# SchV2-4cap.net
KiCad netlist of a schematic drawn in Altium Designer
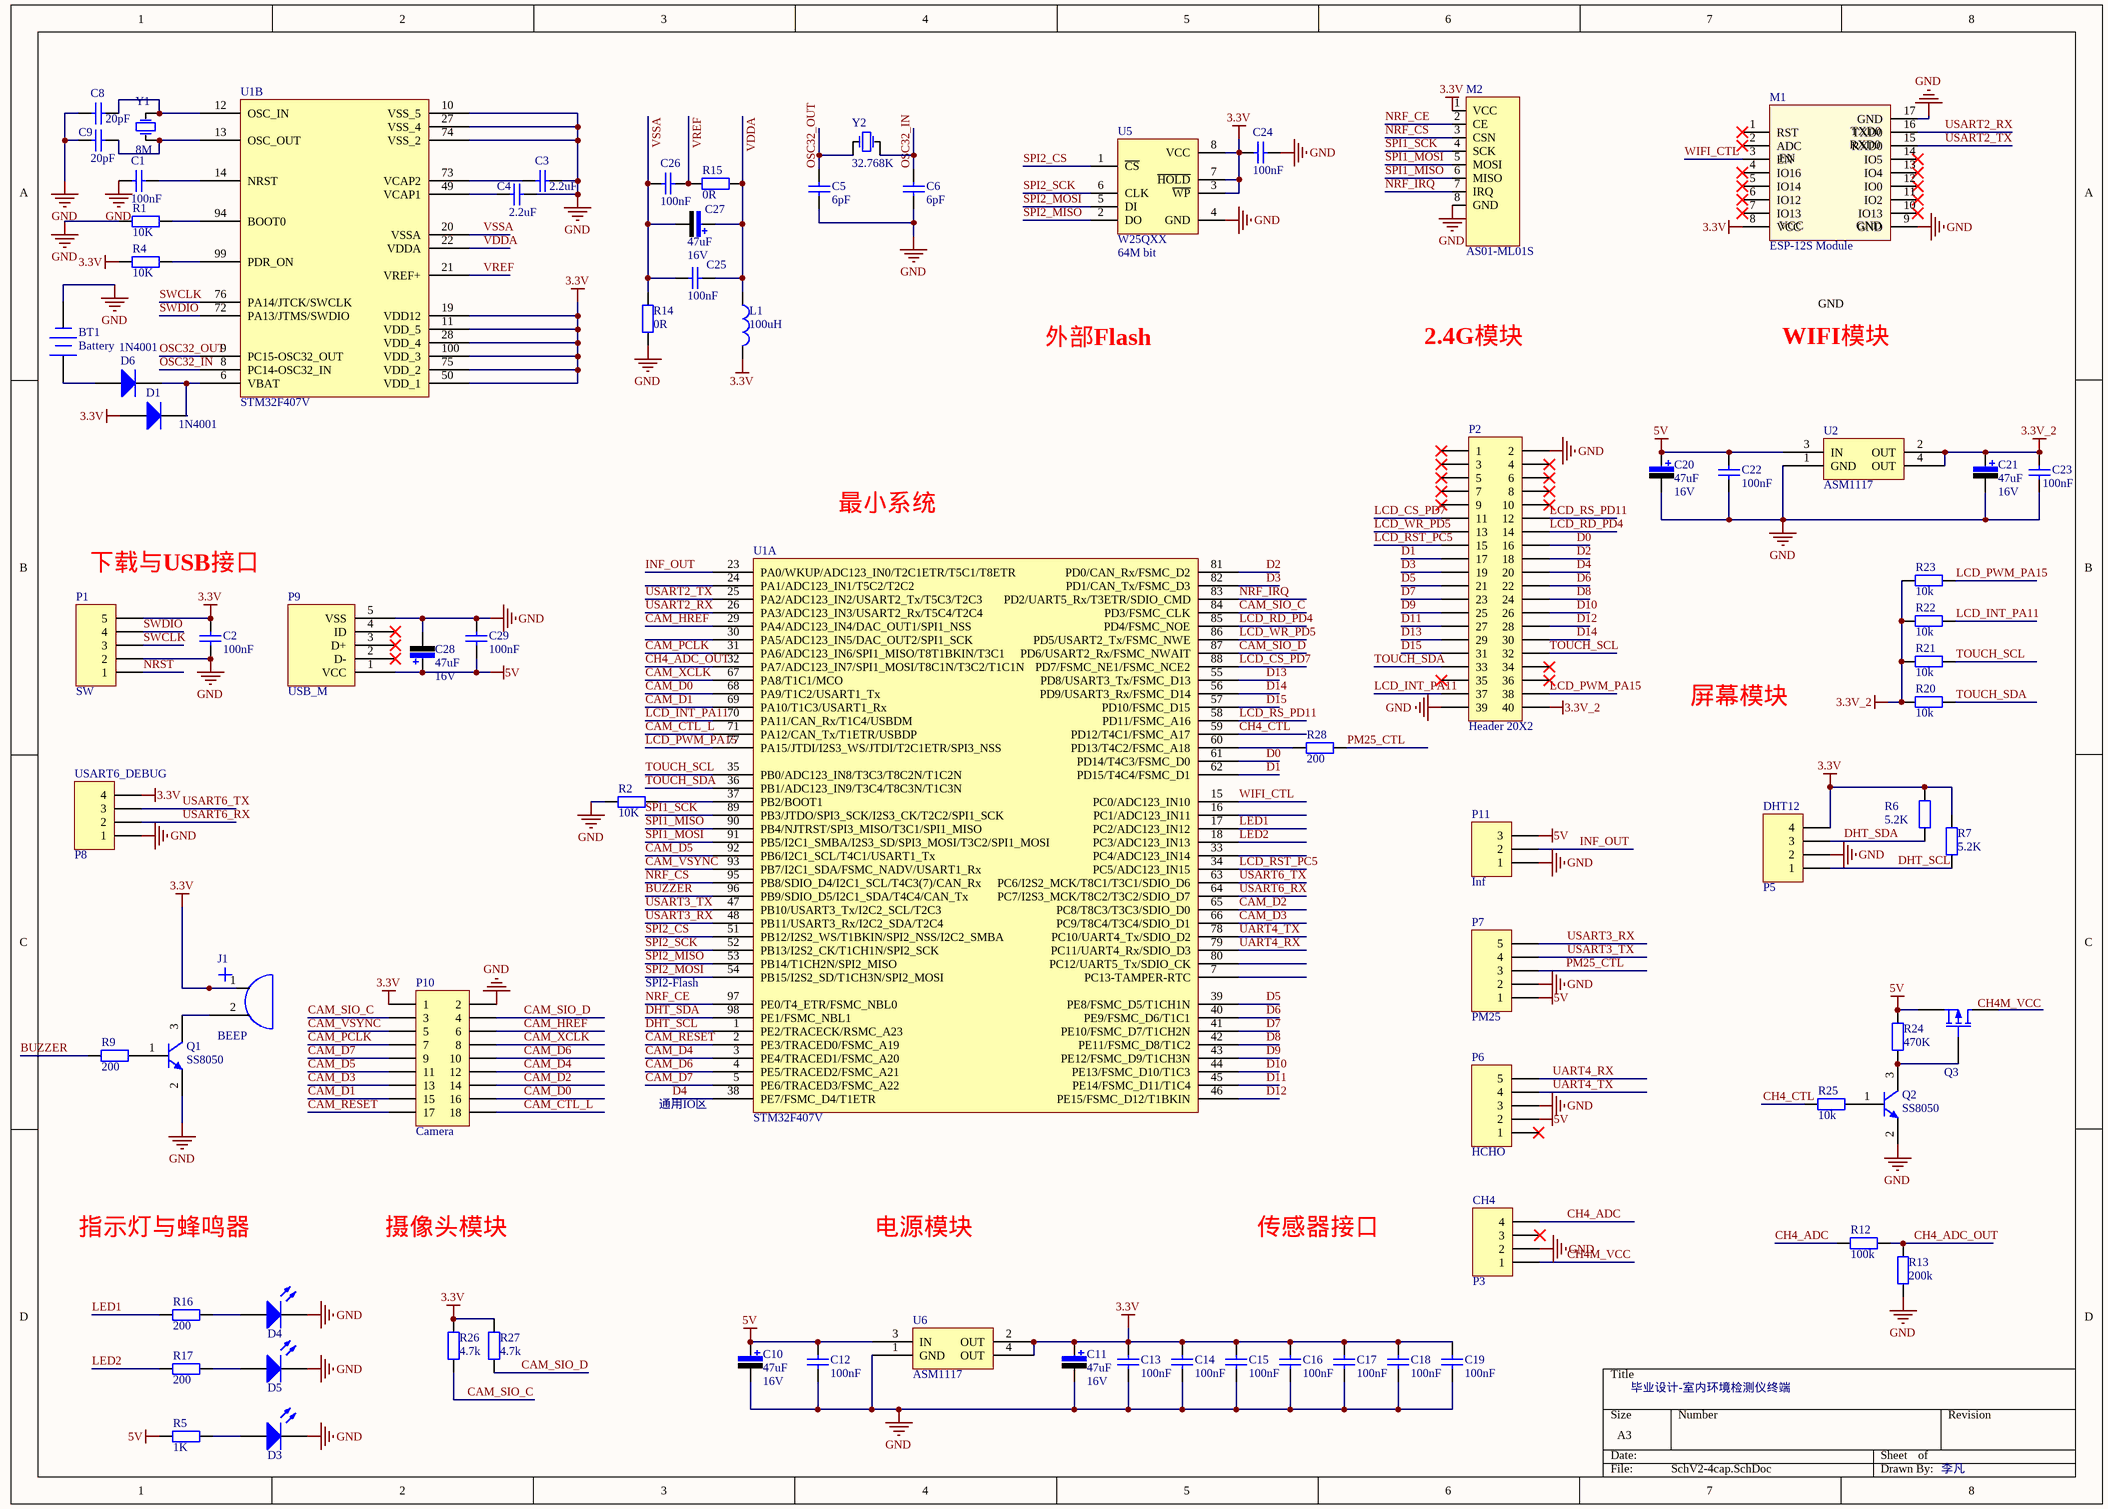
[diagram p0: SchV2-4cap.SchDoc]

(export (version "E")
  (design (tool "Eeschema 10.0.6"))
  (components
    (comp (ref "BT1")
      (value "Battery")
      (footprint "CR1220")
      (description "备份电池")
      (libsource (lib "Fszhang") (part "Battery"))
    )
    (comp (ref "C1")
      (value "100nF")
      (footprint "C-RAD-0603")
      (description "无极性电容")
      (fields (field (name "Comment") "Cap"))
      (libsource (lib "Fszhang") (part "Cap"))
    )
    (comp (ref "C2")
      (value "100nF")
      (footprint "C-RAD-0603")
      (description "无极性电容")
      (fields (field (name "Comment") "Cap"))
      (libsource (lib "Fszhang") (part "Cap"))
    )
    (comp (ref "C3")
      (value "2.2uF")
      (footprint "C-RAD-0603")
      (description "无极性电容")
      (fields (field (name "Comment") "Cap"))
      (libsource (lib "Fszhang") (part "Cap"))
    )
    (comp (ref "C4")
      (value "2.2uF")
      (footprint "C-RAD-0603")
      (description "无极性电容")
      (fields (field (name "Comment") "Cap"))
      (libsource (lib "Fszhang") (part "Cap"))
    )
    (comp (ref "C5")
      (value "6pF")
      (footprint "C-RAD-0603")
      (description "无极性电容")
      (fields (field (name "Comment") "Cap"))
      (libsource (lib "Fszhang") (part "Cap"))
    )
    (comp (ref "C6")
      (value "6pF")
      (footprint "C-RAD-0603")
      (description "无极性电容")
      (fields (field (name "Comment") "Cap"))
      (libsource (lib "Fszhang") (part "Cap"))
    )
    (comp (ref "C8")
      (value "20pF")
      (footprint "C-RAD-0603")
      (description "无极性电容")
      (fields (field (name "Comment") "Cap"))
      (libsource (lib "Fszhang") (part "Cap"))
    )
    (comp (ref "C9")
      (value "20pF")
      (footprint "C-RAD-0603")
      (description "无极性电容")
      (fields (field (name "Comment") "Cap"))
      (libsource (lib "Fszhang") (part "Cap"))
    )
    (comp (ref "C10")
      (value "47uF")
      (footprint "CAP-3528")
      (description "极性电解电容")
      (fields (field (name "VOL") "16V") (field (name "Comment") "Cap Pol"))
      (libsource (lib "Fszhang") (part "Cap Pol"))
    )
    (comp (ref "C11")
      (value "47uF")
      (footprint "CAP-3528")
      (description "极性电解电容")
      (fields (field (name "VOL") "16V") (field (name "Comment") "Cap Pol"))
      (libsource (lib "Fszhang") (part "Cap Pol"))
    )
    (comp (ref "C12")
      (value "100nF")
      (footprint "C-RAD-0603")
      (description "无极性电容")
      (fields (field (name "Comment") "Cap"))
      (libsource (lib "Fszhang") (part "Cap"))
    )
    (comp (ref "C13")
      (value "100nF")
      (footprint "C-RAD-0603")
      (description "无极性电容")
      (fields (field (name "Comment") "Cap"))
      (libsource (lib "Fszhang") (part "Cap"))
    )
    (comp (ref "C14")
      (value "100nF")
      (footprint "C-RAD-0603")
      (description "无极性电容")
      (fields (field (name "Comment") "Cap"))
      (libsource (lib "Fszhang") (part "Cap"))
    )
    (comp (ref "C15")
      (value "100nF")
      (footprint "C-RAD-0603")
      (description "无极性电容")
      (fields (field (name "Comment") "Cap"))
      (libsource (lib "Fszhang") (part "Cap"))
    )
    (comp (ref "C16")
      (value "100nF")
      (footprint "C-RAD-0603")
      (description "无极性电容")
      (fields (field (name "Comment") "Cap"))
      (libsource (lib "Fszhang") (part "Cap"))
    )
    (comp (ref "C17")
      (value "100nF")
      (footprint "C-RAD-0603")
      (description "无极性电容")
      (fields (field (name "Comment") "Cap"))
      (libsource (lib "Fszhang") (part "Cap"))
    )
    (comp (ref "C18")
      (value "100nF")
      (footprint "C-RAD-0603")
      (description "无极性电容")
      (fields (field (name "Comment") "Cap"))
      (libsource (lib "Fszhang") (part "Cap"))
    )
    (comp (ref "C19")
      (value "100nF")
      (footprint "C-RAD-0603")
      (description "无极性电容")
      (fields (field (name "Comment") "Cap"))
      (libsource (lib "Fszhang") (part "Cap"))
    )
    (comp (ref "C20")
      (value "47uF")
      (footprint "CAP-3528")
      (description "极性电解电容")
      (fields (field (name "VOL") "16V") (field (name "Comment") "Cap Pol"))
      (libsource (lib "Fszhang") (part "Cap Pol"))
    )
    (comp (ref "C21")
      (value "47uF")
      (footprint "CAP-3528")
      (description "极性电解电容")
      (fields (field (name "VOL") "16V") (field (name "Comment") "Cap Pol"))
      (libsource (lib "Fszhang") (part "Cap Pol"))
    )
    (comp (ref "C22")
      (value "100nF")
      (footprint "C-RAD-0603")
      (description "无极性电容")
      (fields (field (name "Comment") "Cap"))
      (libsource (lib "Fszhang") (part "Cap"))
    )
    (comp (ref "C23")
      (value "100nF")
      (footprint "C-RAD-0603")
      (description "无极性电容")
      (fields (field (name "Comment") "Cap"))
      (libsource (lib "Fszhang") (part "Cap"))
    )
    (comp (ref "C24")
      (value "100nF")
      (footprint "C-RAD-0603")
      (description "无极性电容")
      (fields (field (name "Comment") "Cap"))
      (libsource (lib "Fszhang") (part "Cap"))
    )
    (comp (ref "C25")
      (value "100nF")
      (footprint "C-RAD-0603")
      (description "无极性电容")
      (fields (field (name "Comment") "Cap"))
      (libsource (lib "Fszhang") (part "Cap"))
    )
    (comp (ref "C26")
      (value "100nF")
      (footprint "C-RAD-0603")
      (description "无极性电容")
      (fields (field (name "Comment") "Cap"))
      (libsource (lib "Fszhang") (part "Cap"))
    )
    (comp (ref "C27")
      (value "47uF")
      (footprint "CAP-3528")
      (description "极性电解电容")
      (fields (field (name "VOL") "16V") (field (name "Comment") "Cap Pol"))
      (libsource (lib "") (part "Cap Pol_2"))
    )
    (comp (ref "C28")
      (value "47uF")
      (footprint "CAP-3528")
      (description "极性电解电容")
      (fields (field (name "VOL") "16V") (field (name "Comment") "Cap Pol"))
      (libsource (lib "") (part "Cap Pol_1"))
    )
    (comp (ref "C29")
      (value "100nF")
      (footprint "C-RAD-0603")
      (description "无极性电容")
      (fields (field (name "Comment") "Cap"))
      (libsource (lib "Fszhang") (part "Cap"))
    )
    (comp (ref "D1")
      (value "Diode")
      (footprint "DIODE-1206")
      (description "二极管")
      (fields (field (name "TYPE") "1N4001"))
      (libsource (lib "Fszhang") (part "Diode"))
    )
    (comp (ref "D3")
      (value "LED0")
      (footprint "LED_0805")
      (description "发光二极管")
      (libsource (lib "Fszhang") (part "LED0"))
    )
    (comp (ref "D4")
      (value "LED0")
      (footprint "LED_0805")
      (description "发光二极管")
      (libsource (lib "Fszhang") (part "LED0"))
    )
    (comp (ref "D5")
      (value "LED0")
      (footprint "LED_0805")
      (description "发光二极管")
      (libsource (lib "Fszhang") (part "LED0"))
    )
    (comp (ref "D6")
      (value "Diode")
      (footprint "DIODE-1206")
      (description "二极管")
      (fields (field (name "TYPE") "1N4001"))
      (libsource (lib "Fszhang") (part "Diode"))
    )
    (comp (ref "J1")
      (value "BEEP")
      (footprint "Beep")
      (description "蜂鸣器")
      (libsource (lib "Fszhang") (part "BEEP"))
    )
    (comp (ref "L1")
      (value "100uH")
      (footprint "0805-1")
      (description "电感")
      (fields (field (name "Comment") "Inductor"))
      (libsource (lib "Fszhang") (part "Inductor"))
    )
    (comp (ref "M1")
      (value "ESP-12S Module")
      (footprint "ESP-12S Module")
      (libsource (lib "ESP-12S Module") (part "ESP-12S Module"))
    )
    (comp (ref "M2")
      (value "AS01-ML01S")
      (footprint "FanliPcbLib:AS01-ML01S")
      (description "贴片2.4G模块")
      (libsource (lib "Schlib") (part "AS01-ML01S"))
    )
    (comp (ref "P1")
      (value "SW")
      (footprint "FanliPcbLib:7-Header_7mm")
      (description "Header, 5-Pin")
      (libsource (lib "Miscellaneous Connectors") (part "Header 5"))
    )
    (comp (ref "P2")
      (value "Header 20X2")
      (footprint "HDR2X20")
      (description "Header, 20-Pin, Dual row")
      (libsource (lib "Miscellaneous Connectors") (part "Header 20X2"))
    )
    (comp (ref "P3")
      (value "CH4")
      (footprint "HDR4X1_A")
      (description "接插件")
      (libsource (lib "Fszhang") (part "Header 4"))
    )
    (comp (ref "P5")
      (value "DHT12")
      (footprint "HDR4X1_A")
      (description "接插件")
      (libsource (lib "Fszhang") (part "Header 4"))
    )
    (comp (ref "P6")
      (value "HCHO")
      (footprint "7-Header_7mm")
      (description "Header, 5-Pin")
      (libsource (lib "Miscellaneous Connectors") (part "Header 5"))
    )
    (comp (ref "P7")
      (value "PM25")
      (footprint "7-Header_7mm")
      (description "Header, 5-Pin")
      (libsource (lib "Miscellaneous Connectors") (part "Header 5"))
    )
    (comp (ref "P8")
      (value "USART6_DEBUG")
      (footprint "HDR4X1_A")
      (description "接插件")
      (libsource (lib "Fszhang") (part "Header 4"))
    )
    (comp (ref "P9")
      (value "USB_M")
      (footprint "USB_MICRO")
      (description "MicroUSB接口")
      (libsource (lib "Fszhang") (part "USB_M"))
    )
    (comp (ref "P10")
      (value "Camera")
      (footprint "HDR2X9")
      (description "Header, 9-Pin, Dual row")
      (libsource (lib "Miscellaneous Connectors") (part "Header 9X2"))
    )
    (comp (ref "P11")
      (value "Inf")
      (footprint "HDR1X3")
      (description "Header, 3-Pin")
      (libsource (lib "Miscellaneous Connectors") (part "Header 3"))
    )
    (comp (ref "Q1")
      (value "SS8050")
      (footprint "SOT-23")
      (description "NPN贴片三极管")
      (libsource (lib "Fszhang") (part "SS8050"))
    )
    (comp (ref "Q2")
      (value "SS8050")
      (footprint "SOT-23")
      (description "NPN贴片三极管")
      (libsource (lib "Fszhang") (part "SS8050"))
    )
    (comp (ref "Q3")
      (value "MOSFET-P")
      (footprint "TO-220AB")
      (description "P-Channel MOSFET")
      (libsource (lib "Fszhang") (part "MOSFET-P"))
    )
    (comp (ref "R1")
      (value "10K")
      (footprint "0603-1")
      (description "贴片电阻")
      (fields (field (name "Comment") "Res1"))
      (libsource (lib "Fszhang") (part "Res1"))
    )
    (comp (ref "R2")
      (value "10K")
      (footprint "0603-1")
      (description "贴片电阻")
      (fields (field (name "Comment") "Res1"))
      (libsource (lib "Fszhang") (part "Res1"))
    )
    (comp (ref "R4")
      (value "10K")
      (footprint "0603-1")
      (description "贴片电阻")
      (fields (field (name "Comment") "Res1"))
      (libsource (lib "Fszhang") (part "Res1"))
    )
    (comp (ref "R5")
      (value "1K")
      (footprint "0603-1")
      (description "贴片电阻")
      (fields (field (name "Comment") "Res1"))
      (libsource (lib "") (part "Res1_2"))
    )
    (comp (ref "R6")
      (value "5.2K")
      (footprint "0603-1")
      (description "贴片电阻")
      (fields (field (name "Comment") "Res1"))
      (libsource (lib "") (part "Res1_1"))
    )
    (comp (ref "R7")
      (value "5.2K")
      (footprint "0603-1")
      (description "贴片电阻")
      (fields (field (name "Comment") "Res1"))
      (libsource (lib "") (part "Res1_1"))
    )
    (comp (ref "R9")
      (value "200")
      (footprint "0603-1")
      (description "贴片电阻")
      (fields (field (name "Comment") "Res1"))
      (libsource (lib "") (part "Res1_2"))
    )
    (comp (ref "R12")
      (value "100k")
      (footprint "0603-1")
      (description "贴片电阻")
      (fields (field (name "Comment") "Res1"))
      (libsource (lib "Fszhang") (part "Res1"))
    )
    (comp (ref "R13")
      (value "200k")
      (footprint "0603-1")
      (description "贴片电阻")
      (fields (field (name "Comment") "Res1"))
      (libsource (lib "") (part "Res1_1"))
    )
    (comp (ref "R14")
      (value "0R")
      (footprint "0603-1")
      (description "贴片电阻")
      (fields (field (name "Comment") "Res1"))
      (libsource (lib "") (part "Res1_1"))
    )
    (comp (ref "R15")
      (value "0R")
      (footprint "0603-1")
      (description "贴片电阻")
      (fields (field (name "Comment") "Res1"))
      (libsource (lib "") (part "Res1_2"))
    )
    (comp (ref "R16")
      (value "200")
      (footprint "0603-1")
      (description "贴片电阻")
      (fields (field (name "Comment") "Res1"))
      (libsource (lib "") (part "Res1_2"))
    )
    (comp (ref "R17")
      (value "200")
      (footprint "0603-1")
      (description "贴片电阻")
      (fields (field (name "Comment") "Res1"))
      (libsource (lib "") (part "Res1_2"))
    )
    (comp (ref "R20")
      (value "10k")
      (footprint "0603-1")
      (description "贴片电阻")
      (fields (field (name "Comment") "Res1"))
      (libsource (lib "") (part "Res1_2"))
    )
    (comp (ref "R21")
      (value "10k")
      (footprint "0603-1")
      (description "贴片电阻")
      (fields (field (name "Comment") "Res1"))
      (libsource (lib "") (part "Res1_2"))
    )
    (comp (ref "R22")
      (value "10k")
      (footprint "0603-1")
      (description "贴片电阻")
      (fields (field (name "Comment") "Res1"))
      (libsource (lib "") (part "Res1_2"))
    )
    (comp (ref "R23")
      (value "10k")
      (footprint "0603-1")
      (description "贴片电阻")
      (fields (field (name "Comment") "Res1"))
      (libsource (lib "") (part "Res1_2"))
    )
    (comp (ref "R24")
      (value "470K")
      (footprint "0603-1")
      (description "贴片电阻")
      (fields (field (name "Comment") "Res1"))
      (libsource (lib "") (part "Res1_1"))
    )
    (comp (ref "R25")
      (value "10k")
      (footprint "0603-1")
      (description "贴片电阻")
      (fields (field (name "Comment") "Res1"))
      (libsource (lib "") (part "Res1_2"))
    )
    (comp (ref "R26")
      (value "4.7k")
      (footprint "0603-1")
      (description "贴片电阻")
      (fields (field (name "Comment") "Res1"))
      (libsource (lib "") (part "Res1_1"))
    )
    (comp (ref "R27")
      (value "4.7k")
      (footprint "0603-1")
      (description "贴片电阻")
      (fields (field (name "Comment") "Res1"))
      (libsource (lib "") (part "Res1_3"))
    )
    (comp (ref "R28")
      (value "200")
      (footprint "0603-1")
      (description "贴片电阻")
      (fields (field (name "Comment") "Res1"))
      (libsource (lib "Fszhang") (part "Res1"))
    )
    (comp (ref "U1")
      (value "STM32F407V")
      (footprint "LQFP-100_M")
      (description "STM32单片机100引脚")
      (libsource (lib "Fszhang") (part "STM32F407V"))
    )
    (comp (ref "U2")
      (value "ASM1117")
      (footprint "SOT-223")
      (description "3.3V稳压芯片")
      (libsource (lib "Fszhang") (part "ASM1117"))
    )
    (comp (ref "U5")
      (value "W25QXX")
      (footprint "SOIC8_W")
      (description "SPI FLASH")
      (fields (field (name "MEMORY") "64M bit"))
      (libsource (lib "Fszhang") (part "W25QXX"))
    )
    (comp (ref "U6")
      (value "ASM1117")
      (footprint "SOT-223")
      (description "3.3V稳压芯片")
      (libsource (lib "Fszhang") (part "ASM1117"))
    )
    (comp (ref "Y1")
      (value "8M")
      (footprint "X-SM49")
      (description "晶振")
      (fields (field (name "Comment") "XTAL"))
      (libsource (lib "Fszhang") (part "XTAL"))
    )
    (comp (ref "Y2")
      (value "32.768K")
      (footprint "MC-306")
      (description "晶振")
      (fields (field (name "Comment") "XTAL"))
      (libsource (lib "Fszhang") (part "XTAL"))
    )
  )
  (nets
    (net (code "1") (name "/BUZZER") (class "Default")
      (node (ref "R9") (pin "2") (pinfunction "2_2") (pintype "passive"))
      (node (ref "U1") (pin "96") (pinfunction "PB9/SDIO_D5/I2C1_SDA/T4C4/CAN_Tx_96") (pintype "passive"))
    )
    (net (code "2") (name "/CAM_CTL_L") (class "Default")
      (node (ref "P10") (pin "18") (pinfunction "18_18") (pintype "passive"))
      (node (ref "U1") (pin "71") (pinfunction "PA12/CAN_Tx/T1ETR/USBDP_71") (pintype "passive"))
    )
    (net (code "3") (name "/CAM_D0") (class "Default")
      (node (ref "P10") (pin "16") (pinfunction "16_16") (pintype "passive"))
      (node (ref "U1") (pin "68") (pinfunction "PA9/T1C2/USART1_Tx_68") (pintype "passive"))
    )
    (net (code "4") (name "/CAM_D1") (class "Default")
      (node (ref "P10") (pin "15") (pinfunction "15_15") (pintype "passive"))
      (node (ref "U1") (pin "69") (pinfunction "PA10/T1C3/USART1_Rx_69") (pintype "passive"))
    )
    (net (code "5") (name "/CAM_D2") (class "Default")
      (node (ref "P10") (pin "14") (pinfunction "14_14") (pintype "passive"))
      (node (ref "U1") (pin "65") (pinfunction "PC8/T8C3/T3C3/SDIO_D0_65") (pintype "passive"))
    )
    (net (code "6") (name "/CAM_D3") (class "Default")
      (node (ref "P10") (pin "13") (pinfunction "13_13") (pintype "passive"))
      (node (ref "U1") (pin "66") (pinfunction "PC9/T8C4/T3C4/SDIO_D1_66") (pintype "passive"))
    )
    (net (code "7") (name "/CAM_D4") (class "Default")
      (node (ref "P10") (pin "12") (pinfunction "12_12") (pintype "passive"))
      (node (ref "U1") (pin "3") (pinfunction "PE4/TRACED1/FSMC_A20_3") (pintype "passive"))
    )
    (net (code "8") (name "/CAM_D5") (class "Default")
      (node (ref "P10") (pin "11") (pinfunction "11_11") (pintype "passive"))
      (node (ref "U1") (pin "92") (pinfunction "PB6/I2C1_SCL/T4C1/USART1_Tx_92") (pintype "passive"))
    )
    (net (code "9") (name "/CAM_D6") (class "Default")
      (node (ref "P10") (pin "10") (pinfunction "10_10") (pintype "passive"))
      (node (ref "U1") (pin "4") (pinfunction "PE5/TRACED2/FSMC_A21_4") (pintype "passive"))
    )
    (net (code "10") (name "/CAM_D7") (class "Default")
      (node (ref "P10") (pin "9") (pinfunction "9_9") (pintype "passive"))
      (node (ref "U1") (pin "5") (pinfunction "PE6/TRACED3/FSMC_A22_5") (pintype "passive"))
    )
    (net (code "11") (name "/CAM_HREF") (class "Default")
      (node (ref "P10") (pin "6") (pinfunction "6_6") (pintype "passive"))
      (node (ref "U1") (pin "29") (pinfunction "PA4/ADC123_IN4/DAC_OUT1/SPI1_NSS_29") (pintype "passive"))
    )
    (net (code "12") (name "/CAM_PCLK") (class "Default")
      (node (ref "P10") (pin "7") (pinfunction "7_7") (pintype "passive"))
      (node (ref "U1") (pin "31") (pinfunction "PA6/ADC123_IN6/SPI1_MISO/T8T1BKIN/T3C1_31") (pintype "passive"))
    )
    (net (code "13") (name "/CAM_RESET") (class "Default")
      (node (ref "P10") (pin "17") (pinfunction "17_17") (pintype "passive"))
      (node (ref "U1") (pin "2") (pinfunction "PE3/TRACED0/FSMC_A19_2") (pintype "passive"))
    )
    (net (code "14") (name "/CAM_SIO_C") (class "Default")
      (node (ref "P10") (pin "3") (pinfunction "3_3") (pintype "passive"))
      (node (ref "R26") (pin "1") (pinfunction "1_1") (pintype "passive"))
      (node (ref "U1") (pin "84") (pinfunction "PD3/FSMC_CLK_84") (pintype "passive"))
    )
    (net (code "15") (name "/CAM_SIO_D") (class "Default")
      (node (ref "P10") (pin "4") (pinfunction "4_4") (pintype "passive"))
      (node (ref "R27") (pin "2") (pinfunction "2_2") (pintype "passive"))
      (node (ref "U1") (pin "87") (pinfunction "PD6/USART2_Rx/FSMC_NWAIT_87") (pintype "passive"))
    )
    (net (code "16") (name "/CAM_VSYNC") (class "Default")
      (node (ref "P10") (pin "5") (pinfunction "5_5") (pintype "passive"))
      (node (ref "U1") (pin "93") (pinfunction "PB7/I2C1_SDA/FSMC_NADV/USART1_Rx_93") (pintype "passive"))
    )
    (net (code "17") (name "/CAM_XCLK") (class "Default")
      (node (ref "P10") (pin "8") (pinfunction "8_8") (pintype "passive"))
      (node (ref "U1") (pin "67") (pinfunction "PA8/T1C1/MCO_67") (pintype "passive"))
    )
    (net (code "18") (name "/CH4M_VCC") (class "Default")
      (node (ref "P3") (pin "1") (pinfunction "1_1") (pintype "passive"))
    )
    (net (code "19") (name "/CH4_ADC") (class "Default")
      (node (ref "P3") (pin "4") (pinfunction "4_4") (pintype "passive"))
      (node (ref "R12") (pin "1") (pinfunction "1_1") (pintype "passive"))
    )
    (net (code "20") (name "/CH4_ADC_OUT") (class "Default")
      (node (ref "R12") (pin "2") (pinfunction "2_2") (pintype "passive"))
      (node (ref "R13") (pin "2") (pinfunction "2_2") (pintype "passive"))
      (node (ref "U1") (pin "32") (pinfunction "PA7/ADC123_IN7/SPI1_MOSI/T8C1N/T3C2/T1C1N_32") (pintype "passive"))
    )
    (net (code "21") (name "/CH4_CTL") (class "Default")
      (node (ref "R25") (pin "2") (pinfunction "2_2") (pintype "passive"))
      (node (ref "U1") (pin "59") (pinfunction "PD12/T4C1/FSMC_A17_59") (pintype "passive"))
    )
    (net (code "22") (name "/D0") (class "Default")
      (node (ref "P2") (pin "16") (pinfunction "16_16") (pintype "passive"))
      (node (ref "U1") (pin "61") (pinfunction "PD14/T4C3/FSMC_D0_61") (pintype "passive"))
    )
    (net (code "23") (name "/D1") (class "Default")
      (node (ref "P2") (pin "17") (pinfunction "17_17") (pintype "passive"))
      (node (ref "U1") (pin "62") (pinfunction "PD15/T4C4/FSMC_D1_62") (pintype "passive"))
    )
    (net (code "24") (name "/D2") (class "Default")
      (node (ref "P2") (pin "18") (pinfunction "18_18") (pintype "passive"))
      (node (ref "U1") (pin "81") (pinfunction "PD0/CAN_Rx/FSMC_D2_81") (pintype "passive"))
    )
    (net (code "25") (name "/D3") (class "Default")
      (node (ref "P2") (pin "19") (pinfunction "19_19") (pintype "passive"))
      (node (ref "U1") (pin "82") (pinfunction "PD1/CAN_Tx/FSMC_D3_82") (pintype "passive"))
    )
    (net (code "26") (name "/D4") (class "Default")
      (node (ref "P2") (pin "20") (pinfunction "20_20") (pintype "passive"))
      (node (ref "U1") (pin "38") (pinfunction "PE7/FSMC_D4/T1ETR_38") (pintype "passive"))
    )
    (net (code "27") (name "/D5") (class "Default")
      (node (ref "P2") (pin "21") (pinfunction "21_21") (pintype "passive"))
      (node (ref "U1") (pin "39") (pinfunction "PE8/FSMC_D5/T1CH1N_39") (pintype "passive"))
    )
    (net (code "28") (name "/D6") (class "Default")
      (node (ref "P2") (pin "22") (pinfunction "22_22") (pintype "passive"))
      (node (ref "U1") (pin "40") (pinfunction "PE9/FSMC_D6/T1C1_40") (pintype "passive"))
    )
    (net (code "29") (name "/D7") (class "Default")
      (node (ref "P2") (pin "23") (pinfunction "23_23") (pintype "passive"))
      (node (ref "U1") (pin "41") (pinfunction "PE10/FSMC_D7/T1CH2N_41") (pintype "passive"))
    )
    (net (code "30") (name "/D8") (class "Default")
      (node (ref "P2") (pin "24") (pinfunction "24_24") (pintype "passive"))
      (node (ref "U1") (pin "42") (pinfunction "PE11/FSMC_D8/T1C2_42") (pintype "passive"))
    )
    (net (code "31") (name "/D9") (class "Default")
      (node (ref "P2") (pin "25") (pinfunction "25_25") (pintype "passive"))
      (node (ref "U1") (pin "43") (pinfunction "PE12/FSMC_D9/T1CH3N_43") (pintype "passive"))
    )
    (net (code "32") (name "/D10") (class "Default")
      (node (ref "P2") (pin "26") (pinfunction "26_26") (pintype "passive"))
      (node (ref "U1") (pin "44") (pinfunction "PE13/FSMC_D10/T1C3_44") (pintype "passive"))
    )
    (net (code "33") (name "/D11") (class "Default")
      (node (ref "P2") (pin "27") (pinfunction "27_27") (pintype "passive"))
      (node (ref "U1") (pin "45") (pinfunction "PE14/FSMC_D11/T1C4_45") (pintype "passive"))
    )
    (net (code "34") (name "/D12") (class "Default")
      (node (ref "P2") (pin "28") (pinfunction "28_28") (pintype "passive"))
      (node (ref "U1") (pin "46") (pinfunction "PE15/FSMC_D12/T1BKIN_46") (pintype "passive"))
    )
    (net (code "35") (name "/D13") (class "Default")
      (node (ref "P2") (pin "29") (pinfunction "29_29") (pintype "passive"))
      (node (ref "U1") (pin "55") (pinfunction "PD8/USART3_Tx/FSMC_D13_55") (pintype "passive"))
    )
    (net (code "36") (name "/D14") (class "Default")
      (node (ref "P2") (pin "30") (pinfunction "30_30") (pintype "passive"))
      (node (ref "U1") (pin "56") (pinfunction "PD9/USART3_Rx/FSMC_D14_56") (pintype "passive"))
    )
    (net (code "37") (name "/D15") (class "Default")
      (node (ref "P2") (pin "31") (pinfunction "31_31") (pintype "passive"))
      (node (ref "U1") (pin "57") (pinfunction "PD10/FSMC_D15_57") (pintype "passive"))
    )
    (net (code "38") (name "/DHT_SCL") (class "Default")
      (node (ref "P5") (pin "1") (pinfunction "1_1") (pintype "passive"))
      (node (ref "R7") (pin "1") (pinfunction "1_1") (pintype "passive"))
      (node (ref "U1") (pin "1") (pinfunction "PE2/TRACECK/RSMC_A23_1") (pintype "passive"))
    )
    (net (code "39") (name "/DHT_SDA") (class "Default")
      (node (ref "P5") (pin "3") (pinfunction "3_3") (pintype "passive"))
      (node (ref "R6") (pin "1") (pinfunction "1_1") (pintype "passive"))
      (node (ref "U1") (pin "98") (pinfunction "PE1/FSMC_NBL1_98") (pintype "passive"))
    )
    (net (code "40") (name "/INF_OUT") (class "Default")
      (node (ref "P11") (pin "2") (pinfunction "2_2") (pintype "passive"))
      (node (ref "U1") (pin "23") (pinfunction "PA0/WKUP/ADC123_IN0/T2C1ETR/T5C1/T8ETR_23") (pintype "passive"))
    )
    (net (code "41") (name "/LCD_CS_PD7") (class "Default")
      (node (ref "P2") (pin "11") (pinfunction "11_11") (pintype "passive"))
      (node (ref "U1") (pin "88") (pinfunction "PD7/FSMC_NE1/FSMC_NCE2_88") (pintype "passive"))
    )
    (net (code "42") (name "/LCD_INT_PA11") (class "Default")
      (node (ref "P2") (pin "37") (pinfunction "37_37") (pintype "passive"))
      (node (ref "R22") (pin "1") (pinfunction "1_1") (pintype "passive"))
      (node (ref "U1") (pin "70") (pinfunction "PA11/CAN_Rx/T1C4/USBDM_70") (pintype "passive"))
    )
    (net (code "43") (name "/LCD_PWM_PA15") (class "Default")
      (node (ref "P2") (pin "38") (pinfunction "38_38") (pintype "passive"))
      (node (ref "R23") (pin "1") (pinfunction "1_1") (pintype "passive"))
      (node (ref "U1") (pin "77") (pinfunction "PA15/JTDI/I2S3_WS/JTDI/T2C1ETR/SPI3_NSS_77") (pintype "passive"))
    )
    (net (code "44") (name "/LCD_RD_PD4") (class "Default")
      (node (ref "P2") (pin "14") (pinfunction "14_14") (pintype "passive"))
      (node (ref "U1") (pin "85") (pinfunction "PD4/FSMC_NOE_85") (pintype "passive"))
    )
    (net (code "45") (name "/LCD_RST_PC5") (class "Default")
      (node (ref "P2") (pin "15") (pinfunction "15_15") (pintype "passive"))
      (node (ref "U1") (pin "34") (pinfunction "PC5/ADC123_IN15_34") (pintype "passive"))
    )
    (net (code "46") (name "/LCD_RS_PD11") (class "Default")
      (node (ref "P2") (pin "12") (pinfunction "12_12") (pintype "passive"))
      (node (ref "U1") (pin "58") (pinfunction "PD11/FSMC_A16_58") (pintype "passive"))
    )
    (net (code "47") (name "/LCD_WR_PD5") (class "Default")
      (node (ref "P2") (pin "13") (pinfunction "13_13") (pintype "passive"))
      (node (ref "U1") (pin "86") (pinfunction "PD5/USART2_Tx/FSMC_NWE_86") (pintype "passive"))
    )
    (net (code "48") (name "/LED1") (class "Default")
      (node (ref "R16") (pin "2") (pinfunction "2_2") (pintype "passive"))
      (node (ref "U1") (pin "17") (pinfunction "PC2/ADC123_IN12_17") (pintype "passive"))
    )
    (net (code "49") (name "/LED2") (class "Default")
      (node (ref "R17") (pin "2") (pinfunction "2_2") (pintype "passive"))
      (node (ref "U1") (pin "18") (pinfunction "PC3/ADC123_IN13_18") (pintype "passive"))
    )
    (net (code "50") (name "/NRF_CE") (class "Default")
      (node (ref "M2") (pin "2") (pinfunction "CE_2") (pintype "passive"))
      (node (ref "U1") (pin "97") (pinfunction "PE0/T4_ETR/FSMC_NBL0_97") (pintype "passive"))
    )
    (net (code "51") (name "/NRF_CS") (class "Default")
      (node (ref "M2") (pin "3") (pinfunction "CSN_3") (pintype "passive"))
      (node (ref "U1") (pin "95") (pinfunction "PB8/SDIO_D4/I2C1_SCL/T4C3(7)/CAN_Rx_95") (pintype "passive"))
    )
    (net (code "52") (name "/NRF_IRQ") (class "Default")
      (node (ref "M2") (pin "7") (pinfunction "IRQ_7") (pintype "passive"))
      (node (ref "U1") (pin "83") (pinfunction "PD2/UART5_Rx/T3ETR/SDIO_CMD_83") (pintype "passive"))
    )
    (net (code "53") (name "/NRST") (class "Default")
      (node (ref "P1") (pin "1") (pinfunction "1_1") (pintype "passive"))
    )
    (net (code "54") (name "/OSC32_IN") (class "Default")
      (node (ref "C6") (pin "2") (pinfunction "2_2") (pintype "passive"))
      (node (ref "U1") (pin "8") (pinfunction "PC14-OSC32_IN_8") (pintype "passive"))
      (node (ref "Y2") (pin "2") (pinfunction "OSC2_2") (pintype "passive"))
    )
    (net (code "55") (name "/OSC32_OUT") (class "Default")
      (node (ref "C5") (pin "2") (pinfunction "2_2") (pintype "passive"))
      (node (ref "U1") (pin "9") (pinfunction "PC15-OSC32_OUT_9") (pintype "passive"))
      (node (ref "Y2") (pin "1") (pinfunction "OSC1_1") (pintype "passive"))
    )
    (net (code "56") (name "/PM25_CTL") (class "Default")
      (node (ref "P7") (pin "3") (pinfunction "3_3") (pintype "passive"))
      (node (ref "R28") (pin "2") (pinfunction "2_2") (pintype "passive"))
    )
    (net (code "57") (name "/SPI1_MISO") (class "Default")
      (node (ref "M2") (pin "6") (pinfunction "MISO_6") (pintype "passive"))
      (node (ref "U1") (pin "90") (pinfunction "PB4/NJTRST/SPI3_MISO/T3C1/SPI1_MISO_90") (pintype "passive"))
    )
    (net (code "58") (name "/SPI1_MOSI") (class "Default")
      (node (ref "M2") (pin "5") (pinfunction "MOSI_5") (pintype "passive"))
      (node (ref "U1") (pin "91") (pinfunction "PB5/I2C1_SMBA/I2S3_SD/SPI3_MOSI/T3C2/SPI1_MOSI_91") (pintype "passive"))
    )
    (net (code "59") (name "/SPI1_SCK") (class "Default")
      (node (ref "M2") (pin "4") (pinfunction "SCK_4") (pintype "passive"))
      (node (ref "U1") (pin "89") (pinfunction "PB3/JTDO/SPI3_SCK/I2S3_CK/T2C2/SPI1_SCK_89") (pintype "passive"))
    )
    (net (code "60") (name "/SPI2_CS") (class "Default")
      (node (ref "U1") (pin "51") (pinfunction "PB12/I2S2_WS/T1BKIN/SPI2_NSS/I2C2_SMBA_51") (pintype "passive"))
      (node (ref "U5") (pin "1") (pinfunction "~{CS}_1") (pintype "passive"))
    )
    (net (code "61") (name "/SPI2_MISO") (class "Default")
      (node (ref "U1") (pin "53") (pinfunction "PB14/T1CH2N/SPI2_MISO_53") (pintype "passive"))
      (node (ref "U5") (pin "2") (pinfunction "DO_2") (pintype "passive"))
    )
    (net (code "62") (name "/SPI2_MOSI") (class "Default")
      (node (ref "U1") (pin "54") (pinfunction "PB15/I2S2_SD/T1CH3N/SPI2_MOSI_54") (pintype "passive"))
      (node (ref "U5") (pin "5") (pinfunction "DI_5") (pintype "passive"))
    )
    (net (code "63") (name "/SPI2_SCK") (class "Default")
      (node (ref "U1") (pin "52") (pinfunction "PB13/I2S2_CK/T1CH1N/SPI2_SCK_52") (pintype "passive"))
      (node (ref "U5") (pin "6") (pinfunction "CLK_6") (pintype "passive"))
    )
    (net (code "64") (name "/SWCLK") (class "Default")
      (node (ref "P1") (pin "3") (pinfunction "3_3") (pintype "passive"))
      (node (ref "U1") (pin "76") (pinfunction "PA14/JTCK/SWCLK_76") (pintype "passive"))
    )
    (net (code "65") (name "/SWDIO") (class "Default")
      (node (ref "P1") (pin "4") (pinfunction "4_4") (pintype "passive"))
      (node (ref "U1") (pin "72") (pinfunction "PA13/JTMS/SWDIO_72") (pintype "passive"))
    )
    (net (code "66") (name "/TOUCH_SCL") (class "Default")
      (node (ref "P2") (pin "32") (pinfunction "32_32") (pintype "passive"))
      (node (ref "R21") (pin "1") (pinfunction "1_1") (pintype "passive"))
      (node (ref "U1") (pin "35") (pinfunction "PB0/ADC123_IN8/T3C3/T8C2N/T1C2N_35") (pintype "passive"))
    )
    (net (code "67") (name "/TOUCH_SDA") (class "Default")
      (node (ref "P2") (pin "33") (pinfunction "33_33") (pintype "passive"))
      (node (ref "R20") (pin "1") (pinfunction "1_1") (pintype "passive"))
      (node (ref "U1") (pin "36") (pinfunction "PB1/ADC123_IN9/T3C4/T8C3N/T1C3N_36") (pintype "passive"))
    )
    (net (code "68") (name "/UART4_RX") (class "Default")
      (node (ref "P6") (pin "5") (pinfunction "5_5") (pintype "passive"))
      (node (ref "U1") (pin "79") (pinfunction "PC11/UART4_Rx/SDIO_D3_79") (pintype "passive"))
    )
    (net (code "69") (name "/UART4_TX") (class "Default")
      (node (ref "P6") (pin "4") (pinfunction "4_4") (pintype "passive"))
      (node (ref "U1") (pin "78") (pinfunction "PC10/UART4_Tx/SDIO_D2_78") (pintype "passive"))
    )
    (net (code "70") (name "/USART2_RX") (class "Default")
      (node (ref "M1") (pin "16") (pinfunction "TXD0_16") (pintype "passive"))
      (node (ref "U1") (pin "26") (pinfunction "PA3/ADC123_IN3/USART2_Rx/T5C4/T2C4_26") (pintype "passive"))
    )
    (net (code "71") (name "/USART2_TX") (class "Default")
      (node (ref "M1") (pin "15") (pinfunction "RXD0_15") (pintype "passive"))
      (node (ref "U1") (pin "25") (pinfunction "PA2/ADC123_IN2/USART2_Tx/T5C3/T2C3_25") (pintype "passive"))
    )
    (net (code "72") (name "/USART3_RX") (class "Default")
      (node (ref "P7") (pin "5") (pinfunction "5_5") (pintype "passive"))
      (node (ref "U1") (pin "48") (pinfunction "PB11/USART3_Rx/I2C2_SDA/T2C4_48") (pintype "passive"))
    )
    (net (code "73") (name "/USART3_TX") (class "Default")
      (node (ref "P7") (pin "4") (pinfunction "4_4") (pintype "passive"))
      (node (ref "U1") (pin "47") (pinfunction "PB10/USART3_Tx/I2C2_SCL/T2C3_47") (pintype "passive"))
    )
    (net (code "74") (name "/USART6_RX") (class "Default")
      (node (ref "P8") (pin "2") (pinfunction "2_2") (pintype "passive"))
      (node (ref "U1") (pin "64") (pinfunction "PC7/I2S3_MCK/T8C2/T3C2/SDIO_D7_64") (pintype "passive"))
    )
    (net (code "75") (name "/USART6_TX") (class "Default")
      (node (ref "P8") (pin "3") (pinfunction "3_3") (pintype "passive"))
      (node (ref "U1") (pin "63") (pinfunction "PC6/I2S2_MCK/T8C1/T3C1/SDIO_D6_63") (pintype "passive"))
    )
    (net (code "76") (name "/VDDA") (class "Default")
      (node (ref "C25") (pin "1") (pinfunction "1_1") (pintype "passive"))
      (node (ref "C27") (pin "1") (pinfunction "1_1") (pintype "passive"))
      (node (ref "L1") (pin "1") (pinfunction "1_1") (pintype "passive"))
      (node (ref "R15") (pin "1") (pinfunction "1_1") (pintype "passive"))
      (node (ref "U1") (pin "22") (pinfunction "VDDA_22") (pintype "passive"))
    )
    (net (code "77") (name "/VREF") (class "Default")
      (node (ref "C26") (pin "1") (pinfunction "1_1") (pintype "passive"))
      (node (ref "R15") (pin "2") (pinfunction "2_2") (pintype "passive"))
      (node (ref "U1") (pin "21") (pinfunction "VREF+_21") (pintype "passive"))
    )
    (net (code "78") (name "/VSSA") (class "Default")
      (node (ref "C25") (pin "2") (pinfunction "2_2") (pintype "passive"))
      (node (ref "C26") (pin "2") (pinfunction "2_2") (pintype "passive"))
      (node (ref "C27") (pin "2") (pinfunction "2_2") (pintype "passive"))
      (node (ref "R14") (pin "2") (pinfunction "2_2") (pintype "passive"))
      (node (ref "U1") (pin "20") (pinfunction "VSSA_20") (pintype "passive"))
    )
    (net (code "79") (name "/WIFI_CTL") (class "Default")
      (node (ref "M1") (pin "3") (pinfunction "EN_3") (pintype "passive"))
      (node (ref "U1") (pin "15") (pinfunction "PC0/ADC123_IN10_15") (pintype "passive"))
    )
    (net (code "80") (name "3.3V") (class "Default")
      (node (ref "C11") (pin "1") (pinfunction "1_1") (pintype "passive"))
      (node (ref "C13") (pin "2") (pinfunction "2_2") (pintype "passive"))
      (node (ref "C14") (pin "2") (pinfunction "2_2") (pintype "passive"))
      (node (ref "C15") (pin "2") (pinfunction "2_2") (pintype "passive"))
      (node (ref "C16") (pin "2") (pinfunction "2_2") (pintype "passive"))
      (node (ref "C17") (pin "2") (pinfunction "2_2") (pintype "passive"))
      (node (ref "C18") (pin "2") (pinfunction "2_2") (pintype "passive"))
      (node (ref "C19") (pin "2") (pinfunction "2_2") (pintype "passive"))
      (node (ref "C2") (pin "2") (pinfunction "2_2") (pintype "passive"))
      (node (ref "C24") (pin "2") (pinfunction "2_2") (pintype "passive"))
      (node (ref "D1") (pin "1") (pinfunction "A_1") (pintype "passive"))
      (node (ref "J1") (pin "1") (pinfunction "0_1") (pintype "passive"))
      (node (ref "L1") (pin "2") (pinfunction "2_2") (pintype "passive"))
      (node (ref "M1") (pin "8") (pinfunction "VCC_8") (pintype "passive"))
      (node (ref "M2") (pin "1") (pinfunction "VCC_1") (pintype "passive"))
      (node (ref "P1") (pin "5") (pinfunction "5_5") (pintype "passive"))
      (node (ref "P10") (pin "1") (pinfunction "1_1") (pintype "passive"))
      (node (ref "P5") (pin "4") (pinfunction "4_4") (pintype "passive"))
      (node (ref "P8") (pin "4") (pinfunction "4_4") (pintype "passive"))
      (node (ref "R26") (pin "2") (pinfunction "2_2") (pintype "passive"))
      (node (ref "R27") (pin "1") (pinfunction "1_1") (pintype "passive"))
      (node (ref "R4") (pin "1") (pinfunction "1_1") (pintype "passive"))
      (node (ref "R6") (pin "2") (pinfunction "2_2") (pintype "passive"))
      (node (ref "R7") (pin "2") (pinfunction "2_2") (pintype "passive"))
      (node (ref "U1") (pin "100") (pinfunction "VDD_3_100") (pintype "passive"))
      (node (ref "U1") (pin "11") (pinfunction "VDD_5_11") (pintype "passive"))
      (node (ref "U1") (pin "19") (pinfunction "VDD12_19") (pintype "passive"))
      (node (ref "U1") (pin "28") (pinfunction "VDD_4_28") (pintype "passive"))
      (node (ref "U1") (pin "50") (pinfunction "VDD_1_50") (pintype "passive"))
      (node (ref "U1") (pin "75") (pinfunction "VDD_2_75") (pintype "passive"))
      (node (ref "U5") (pin "3") (pinfunction "~{WP}_3") (pintype "passive"))
      (node (ref "U5") (pin "7") (pinfunction "~{HOLD}_7") (pintype "passive"))
      (node (ref "U5") (pin "8") (pinfunction "VCC_8") (pintype "passive"))
      (node (ref "U6") (pin "2") (pinfunction "OUT_2") (pintype "passive"))
      (node (ref "U6") (pin "4") (pinfunction "OUT_4") (pintype "passive"))
    )
    (net (code "81") (name "3.3V_2") (class "Default")
      (node (ref "C21") (pin "1") (pinfunction "1_1") (pintype "passive"))
      (node (ref "C23") (pin "2") (pinfunction "2_2") (pintype "passive"))
      (node (ref "P2") (pin "40") (pinfunction "40_40") (pintype "passive"))
      (node (ref "R20") (pin "2") (pinfunction "2_2") (pintype "passive"))
      (node (ref "R21") (pin "2") (pinfunction "2_2") (pintype "passive"))
      (node (ref "R22") (pin "2") (pinfunction "2_2") (pintype "passive"))
      (node (ref "R23") (pin "2") (pinfunction "2_2") (pintype "passive"))
      (node (ref "U2") (pin "2") (pinfunction "OUT_2") (pintype "passive"))
      (node (ref "U2") (pin "4") (pinfunction "OUT_4") (pintype "passive"))
    )
    (net (code "82") (name "5V") (class "Default")
      (node (ref "C10") (pin "1") (pinfunction "1_1") (pintype "passive"))
      (node (ref "C12") (pin "2") (pinfunction "2_2") (pintype "passive"))
      (node (ref "C20") (pin "1") (pinfunction "1_1") (pintype "passive"))
      (node (ref "C22") (pin "2") (pinfunction "2_2") (pintype "passive"))
      (node (ref "C28") (pin "1") (pinfunction "1_1") (pintype "passive"))
      (node (ref "C29") (pin "2") (pinfunction "2_2") (pintype "passive"))
      (node (ref "P11") (pin "3") (pinfunction "3_3") (pintype "passive"))
      (node (ref "P6") (pin "2") (pinfunction "2_2") (pintype "passive"))
      (node (ref "P7") (pin "1") (pinfunction "1_1") (pintype "passive"))
      (node (ref "P9") (pin "1") (pinfunction "VCC_1") (pintype "passive"))
      (node (ref "Q3") (pin "S") (pinfunction "S_S") (pintype "passive"))
      (node (ref "R24") (pin "2") (pinfunction "2_2") (pintype "passive"))
      (node (ref "R5") (pin "2") (pinfunction "2_2") (pintype "passive"))
      (node (ref "U2") (pin "3") (pinfunction "IN_3") (pintype "passive"))
      (node (ref "U6") (pin "3") (pinfunction "IN_3") (pintype "passive"))
    )
    (net (code "83") (name "GND") (class "Default")
      (node (ref "BT1") (pin "2") (pinfunction "-_2") (pintype "passive"))
      (node (ref "C1") (pin "2") (pinfunction "2_2") (pintype "passive"))
      (node (ref "C10") (pin "2") (pinfunction "2_2") (pintype "passive"))
      (node (ref "C11") (pin "2") (pinfunction "2_2") (pintype "passive"))
      (node (ref "C12") (pin "1") (pinfunction "1_1") (pintype "passive"))
      (node (ref "C13") (pin "1") (pinfunction "1_1") (pintype "passive"))
      (node (ref "C14") (pin "1") (pinfunction "1_1") (pintype "passive"))
      (node (ref "C15") (pin "1") (pinfunction "1_1") (pintype "passive"))
      (node (ref "C16") (pin "1") (pinfunction "1_1") (pintype "passive"))
      (node (ref "C17") (pin "1") (pinfunction "1_1") (pintype "passive"))
      (node (ref "C18") (pin "1") (pinfunction "1_1") (pintype "passive"))
      (node (ref "C19") (pin "1") (pinfunction "1_1") (pintype "passive"))
      (node (ref "C2") (pin "1") (pinfunction "1_1") (pintype "passive"))
      (node (ref "C20") (pin "2") (pinfunction "2_2") (pintype "passive"))
      (node (ref "C21") (pin "2") (pinfunction "2_2") (pintype "passive"))
      (node (ref "C22") (pin "1") (pinfunction "1_1") (pintype "passive"))
      (node (ref "C23") (pin "1") (pinfunction "1_1") (pintype "passive"))
      (node (ref "C24") (pin "1") (pinfunction "1_1") (pintype "passive"))
      (node (ref "C28") (pin "2") (pinfunction "2_2") (pintype "passive"))
      (node (ref "C29") (pin "1") (pinfunction "1_1") (pintype "passive"))
      (node (ref "C3") (pin "2") (pinfunction "2_2") (pintype "passive"))
      (node (ref "C4") (pin "2") (pinfunction "2_2") (pintype "passive"))
      (node (ref "C5") (pin "1") (pinfunction "1_1") (pintype "passive"))
      (node (ref "C6") (pin "1") (pinfunction "1_1") (pintype "passive"))
      (node (ref "C8") (pin "1") (pinfunction "1_1") (pintype "passive"))
      (node (ref "C9") (pin "1") (pinfunction "1_1") (pintype "passive"))
      (node (ref "D3") (pin "2") (pinfunction "K_2") (pintype "passive"))
      (node (ref "D4") (pin "2") (pinfunction "K_2") (pintype "passive"))
      (node (ref "D5") (pin "2") (pinfunction "K_2") (pintype "passive"))
      (node (ref "M1") (pin "17") (pinfunction "GND_17") (pintype "passive"))
      (node (ref "M1") (pin "9") (pinfunction "GND_9") (pintype "passive"))
      (node (ref "M2") (pin "8") (pinfunction "GND_8") (pintype "passive"))
      (node (ref "P1") (pin "2") (pinfunction "2_2") (pintype "passive"))
      (node (ref "P10") (pin "2") (pinfunction "2_2") (pintype "passive"))
      (node (ref "P11") (pin "1") (pinfunction "1_1") (pintype "passive"))
      (node (ref "P2") (pin "2") (pinfunction "2_2") (pintype "passive"))
      (node (ref "P2") (pin "39") (pinfunction "39_39") (pintype "passive"))
      (node (ref "P3") (pin "2") (pinfunction "2_2") (pintype "passive"))
      (node (ref "P5") (pin "2") (pinfunction "2_2") (pintype "passive"))
      (node (ref "P6") (pin "3") (pinfunction "3_3") (pintype "passive"))
      (node (ref "P7") (pin "2") (pinfunction "2_2") (pintype "passive"))
      (node (ref "P8") (pin "1") (pinfunction "1_1") (pintype "passive"))
      (node (ref "P9") (pin "5") (pinfunction "VSS_5") (pintype "passive"))
      (node (ref "Q1") (pin "2") (pinfunction "E_2") (pintype "passive"))
      (node (ref "Q2") (pin "2") (pinfunction "E_2") (pintype "passive"))
      (node (ref "R1") (pin "1") (pinfunction "1_1") (pintype "passive"))
      (node (ref "R13") (pin "1") (pinfunction "1_1") (pintype "passive"))
      (node (ref "R14") (pin "1") (pinfunction "1_1") (pintype "passive"))
      (node (ref "R2") (pin "1") (pinfunction "1_1") (pintype "passive"))
      (node (ref "U1") (pin "10") (pinfunction "VSS_5_10") (pintype "passive"))
      (node (ref "U1") (pin "27") (pinfunction "VSS_4_27") (pintype "passive"))
      (node (ref "U1") (pin "74") (pinfunction "VSS_2_74") (pintype "passive"))
      (node (ref "U2") (pin "1") (pinfunction "GND_1") (pintype "passive"))
      (node (ref "U5") (pin "4") (pinfunction "GND_4") (pintype "passive"))
      (node (ref "U6") (pin "1") (pinfunction "GND_1") (pintype "passive"))
    )
    (net (code "84") (name "Net-(BT1-+)") (class "Default")
      (node (ref "BT1") (pin "1") (pinfunction "+_1") (pintype "passive"))
      (node (ref "D6") (pin "1") (pinfunction "A_1") (pintype "passive"))
    )
    (net (code "85") (name "Net-(D1-K)") (class "Default")
      (node (ref "D1") (pin "2") (pinfunction "K_2") (pintype "passive"))
      (node (ref "D6") (pin "2") (pinfunction "K_2") (pintype "passive"))
      (node (ref "U1") (pin "6") (pinfunction "VBAT_6") (pintype "passive"))
    )
    (net (code "86") (name "Net-(D3-A)") (class "Default")
      (node (ref "D3") (pin "1") (pinfunction "A_1") (pintype "passive"))
      (node (ref "R5") (pin "1") (pinfunction "1_1") (pintype "passive"))
    )
    (net (code "87") (name "Net-(D4-A)") (class "Default")
      (node (ref "D4") (pin "1") (pinfunction "A_1") (pintype "passive"))
      (node (ref "R16") (pin "1") (pinfunction "1_1") (pintype "passive"))
    )
    (net (code "88") (name "Net-(D5-A)") (class "Default")
      (node (ref "D5") (pin "1") (pinfunction "A_1") (pintype "passive"))
      (node (ref "R17") (pin "1") (pinfunction "1_1") (pintype "passive"))
    )
    (net (code "89") (name "Net-(J1-1)") (class "Default")
      (node (ref "J1") (pin "2") (pinfunction "1_2") (pintype "passive"))
      (node (ref "Q1") (pin "3") (pinfunction "C_3") (pintype "passive"))
    )
    (net (code "90") (name "Net-(Q1-B)") (class "Default")
      (node (ref "Q1") (pin "1") (pinfunction "B_1") (pintype "passive"))
      (node (ref "R9") (pin "1") (pinfunction "1_1") (pintype "passive"))
    )
    (net (code "91") (name "Net-(Q2-C)") (class "Default")
      (node (ref "Q2") (pin "3") (pinfunction "C_3") (pintype "passive"))
      (node (ref "Q3") (pin "G") (pinfunction "G_G") (pintype "passive"))
      (node (ref "R24") (pin "1") (pinfunction "1_1") (pintype "passive"))
    )
    (net (code "92") (name "Net-(U1A-PB2{slash}BOOT1)") (class "Default")
      (node (ref "R2") (pin "2") (pinfunction "2_2") (pintype "passive"))
      (node (ref "U1") (pin "37") (pinfunction "PB2/BOOT1_37") (pintype "passive"))
    )
    (net (code "93") (name "Net-(U1A-PD13{slash}T4C2{slash}FSMC_A18)") (class "Default")
      (node (ref "R28") (pin "1") (pinfunction "1_1") (pintype "passive"))
      (node (ref "U1") (pin "60") (pinfunction "PD13/T4C2/FSMC_A18_60") (pintype "passive"))
    )
    (net (code "94") (name "Net-(U1B-BOOT0)") (class "Default")
      (node (ref "R1") (pin "2") (pinfunction "2_2") (pintype "passive"))
      (node (ref "U1") (pin "94") (pinfunction "BOOT0_94") (pintype "passive"))
    )
    (net (code "95") (name "Net-(U1B-NRST)") (class "Default")
      (node (ref "C1") (pin "1") (pinfunction "1_1") (pintype "passive"))
      (node (ref "U1") (pin "14") (pinfunction "NRST_14") (pintype "passive"))
    )
    (net (code "96") (name "Net-(U1B-OSC_IN)") (class "Default")
      (node (ref "C8") (pin "2") (pinfunction "2_2") (pintype "passive"))
      (node (ref "U1") (pin "12") (pinfunction "OSC_IN_12") (pintype "passive"))
      (node (ref "Y1") (pin "2") (pinfunction "OSC2_2") (pintype "passive"))
    )
    (net (code "97") (name "Net-(U1B-OSC_OUT)") (class "Default")
      (node (ref "C9") (pin "2") (pinfunction "2_2") (pintype "passive"))
      (node (ref "U1") (pin "13") (pinfunction "OSC_OUT_13") (pintype "passive"))
      (node (ref "Y1") (pin "1") (pinfunction "OSC1_1") (pintype "passive"))
    )
    (net (code "98") (name "Net-(U1B-PDR_ON)") (class "Default")
      (node (ref "R4") (pin "2") (pinfunction "2_2") (pintype "passive"))
      (node (ref "U1") (pin "99") (pinfunction "PDR_ON_99") (pintype "passive"))
    )
    (net (code "99") (name "Net-(U1B-VCAP1)") (class "Default")
      (node (ref "C4") (pin "1") (pinfunction "1_1") (pintype "passive"))
      (node (ref "U1") (pin "49") (pinfunction "VCAP1_49") (pintype "passive"))
    )
    (net (code "100") (name "Net-(U1B-VCAP2)") (class "Default")
      (node (ref "C3") (pin "1") (pinfunction "1_1") (pintype "passive"))
      (node (ref "U1") (pin "73") (pinfunction "VCAP2_73") (pintype "passive"))
    )
    (net (code "101") (name "unconnected-(M1-ADC-Pad2)") (class "Default")
      (node (ref "M1") (pin "2") (pinfunction "ADC_2") (pintype "passive+no_connect"))
    )
    (net (code "102") (name "unconnected-(M1-IO0-Pad12)") (class "Default")
      (node (ref "M1") (pin "12") (pinfunction "IO0_12") (pintype "passive+no_connect"))
    )
    (net (code "103") (name "unconnected-(M1-IO2-Pad11)") (class "Default")
      (node (ref "M1") (pin "11") (pinfunction "IO2_11") (pintype "passive+no_connect"))
    )
    (net (code "104") (name "unconnected-(M1-IO4-Pad13)") (class "Default")
      (node (ref "M1") (pin "13") (pinfunction "IO4_13") (pintype "passive+no_connect"))
    )
    (net (code "105") (name "unconnected-(M1-IO5-Pad14)") (class "Default")
      (node (ref "M1") (pin "14") (pinfunction "IO5_14") (pintype "passive+no_connect"))
    )
    (net (code "106") (name "unconnected-(M1-IO12-Pad6)") (class "Default")
      (node (ref "M1") (pin "6") (pinfunction "IO12_6") (pintype "passive+no_connect"))
    )
    (net (code "107") (name "unconnected-(M1-IO13-Pad7)") (class "Default")
      (node (ref "M1") (pin "7") (pinfunction "IO13_7") (pintype "passive+no_connect"))
    )
    (net (code "108") (name "unconnected-(M1-IO13-Pad10)") (class "Default")
      (node (ref "M1") (pin "10") (pinfunction "IO13_10") (pintype "passive+no_connect"))
    )
    (net (code "109") (name "unconnected-(M1-IO14-Pad5)") (class "Default")
      (node (ref "M1") (pin "5") (pinfunction "IO14_5") (pintype "passive+no_connect"))
    )
    (net (code "110") (name "unconnected-(M1-IO16-Pad4)") (class "Default")
      (node (ref "M1") (pin "4") (pinfunction "IO16_4") (pintype "passive+no_connect"))
    )
    (net (code "111") (name "unconnected-(M1-RST-Pad1)") (class "Default")
      (node (ref "M1") (pin "1") (pinfunction "RST_1") (pintype "passive+no_connect"))
    )
    (net (code "112") (name "unconnected-(P2-Pad1)") (class "Default")
      (node (ref "P2") (pin "1") (pinfunction "1_1") (pintype "passive+no_connect"))
    )
    (net (code "113") (name "unconnected-(P2-Pad3)") (class "Default")
      (node (ref "P2") (pin "3") (pinfunction "3_3") (pintype "passive+no_connect"))
    )
    (net (code "114") (name "unconnected-(P2-Pad4)") (class "Default")
      (node (ref "P2") (pin "4") (pinfunction "4_4") (pintype "passive+no_connect"))
    )
    (net (code "115") (name "unconnected-(P2-Pad5)") (class "Default")
      (node (ref "P2") (pin "5") (pinfunction "5_5") (pintype "passive+no_connect"))
    )
    (net (code "116") (name "unconnected-(P2-Pad6)") (class "Default")
      (node (ref "P2") (pin "6") (pinfunction "6_6") (pintype "passive+no_connect"))
    )
    (net (code "117") (name "unconnected-(P2-Pad7)") (class "Default")
      (node (ref "P2") (pin "7") (pinfunction "7_7") (pintype "passive+no_connect"))
    )
    (net (code "118") (name "unconnected-(P2-Pad8)") (class "Default")
      (node (ref "P2") (pin "8") (pinfunction "8_8") (pintype "passive+no_connect"))
    )
    (net (code "119") (name "unconnected-(P2-Pad9)") (class "Default")
      (node (ref "P2") (pin "9") (pinfunction "9_9") (pintype "passive+no_connect"))
    )
    (net (code "120") (name "unconnected-(P2-Pad10)") (class "Default")
      (node (ref "P2") (pin "10") (pinfunction "10_10") (pintype "passive+no_connect"))
    )
    (net (code "121") (name "unconnected-(P2-Pad34)") (class "Default")
      (node (ref "P2") (pin "34") (pinfunction "34_34") (pintype "passive+no_connect"))
    )
    (net (code "122") (name "unconnected-(P2-Pad35)") (class "Default")
      (node (ref "P2") (pin "35") (pinfunction "35_35") (pintype "passive+no_connect"))
    )
    (net (code "123") (name "unconnected-(P2-Pad36)") (class "Default")
      (node (ref "P2") (pin "36") (pinfunction "36_36") (pintype "passive+no_connect"))
    )
    (net (code "124") (name "unconnected-(P3-Pad3)") (class "Default")
      (node (ref "P3") (pin "3") (pinfunction "3_3") (pintype "passive+no_connect"))
    )
    (net (code "125") (name "unconnected-(P6-Pad1)") (class "Default")
      (node (ref "P6") (pin "1") (pinfunction "1_1") (pintype "passive+no_connect"))
    )
    (net (code "126") (name "unconnected-(P9-D+-Pad3)") (class "Default")
      (node (ref "P9") (pin "3") (pinfunction "D+_3") (pintype "passive+no_connect"))
    )
    (net (code "127") (name "unconnected-(P9-D--Pad2)") (class "Default")
      (node (ref "P9") (pin "2") (pinfunction "D-_2") (pintype "passive+no_connect"))
    )
    (net (code "128") (name "unconnected-(P9-ID-Pad4)") (class "Default")
      (node (ref "P9") (pin "4") (pinfunction "ID_4") (pintype "passive+no_connect"))
    )
    (net (code "129") (name "unconnected-(Q2-B-Pad1)") (class "Default")
      (node (ref "Q2") (pin "1") (pinfunction "B_1") (pintype "passive"))
    )
    (net (code "130") (name "unconnected-(Q3-PadD)") (class "Default")
      (node (ref "Q3") (pin "D") (pinfunction "D_D") (pintype "passive"))
    )
    (net (code "131") (name "unconnected-(R25-Pad1)") (class "Default")
      (node (ref "R25") (pin "1") (pinfunction "1_1") (pintype "passive"))
    )
    (net (code "132") (name "unconnected-(U1A-PA1{slash}ADC123_IN1{slash}T5C2{slash}T2C2-Pad24)") (class "Default")
      (node (ref "U1") (pin "24") (pinfunction "PA1/ADC123_IN1/T5C2/T2C2_24") (pintype "passive"))
    )
    (net (code "133") (name "unconnected-(U1A-PA5{slash}ADC123_IN5{slash}DAC_OUT2{slash}SPI1_SCK-Pad30)") (class "Default")
      (node (ref "U1") (pin "30") (pinfunction "PA5/ADC123_IN5/DAC_OUT2/SPI1_SCK_30") (pintype "passive"))
    )
    (net (code "134") (name "unconnected-(U1A-PC1{slash}ADC123_IN11-Pad16)") (class "Default")
      (node (ref "U1") (pin "16") (pinfunction "PC1/ADC123_IN11_16") (pintype "passive"))
    )
    (net (code "135") (name "unconnected-(U1A-PC4{slash}ADC123_IN14-Pad33)") (class "Default")
      (node (ref "U1") (pin "33") (pinfunction "PC4/ADC123_IN14_33") (pintype "passive"))
    )
    (net (code "136") (name "unconnected-(U1A-PC12{slash}UART5_Tx{slash}SDIO_CK-Pad80)") (class "Default")
      (node (ref "U1") (pin "80") (pinfunction "PC12/UART5_Tx/SDIO_CK_80") (pintype "passive"))
    )
    (net (code "137") (name "unconnected-(U1A-PC13-TAMPER-RTC-Pad7)") (class "Default")
      (node (ref "U1") (pin "7") (pinfunction "PC13-TAMPER-RTC_7") (pintype "passive"))
    )
  )
)
